# TP_IHM_BUZZER.net
KiCad netlist of a schematic drawn in Altium Designer
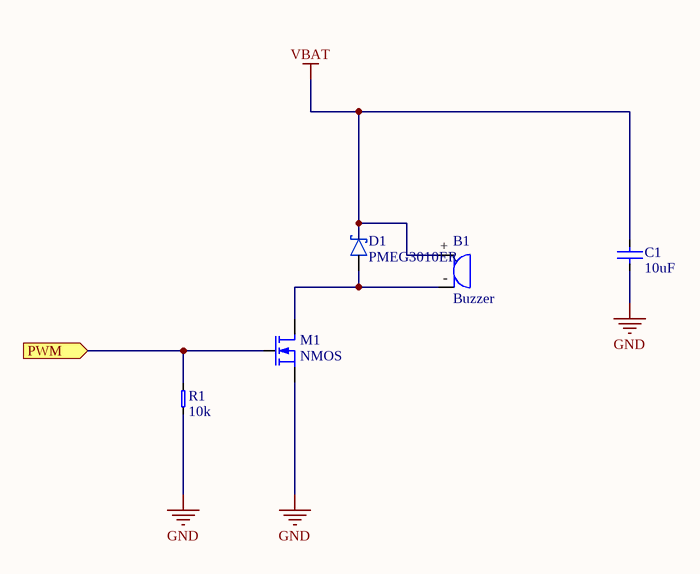
[diagram p0: TP_IHM_BUZZER.SchDoc]

(export (version "E")
  (design (tool "Eeschema 10.0.6"))
  (components
    (comp (ref "B1")
      (value "Buzzer")
      (footprint "SD160709")
      (description "TDK SD160709 Buzzer")
      (libsource (lib "TpGiven") (part "SD160709"))
    )
    (comp (ref "C1")
      (value "10uF")
      (footprint "0603_CAP_LD")
      (description "Ceramic Capacitor")
      (fields (field (name "Comment") "CerCap"))
      (libsource (lib "TpGiven") (part "CerCap"))
    )
    (comp (ref "D1")
      (value "PMEG3010ER")
      (footprint "SOD123W")
      (description "Nexperia 1A low Vf Mega Schottky barrier rectifier")
      (libsource (lib "TpGivenLib") (part "Schottky_PMEG3010ER"))
    )
    (comp (ref "M1")
      (value "NMOS")
      (footprint "MOSFET-SOT23")
      (description "N MOSFET")
      (libsource (lib "TpGiven") (part "N-MOSFET"))
    )
    (comp (ref "R1")
      (value "10k")
      (footprint "0603_RES_LD")
      (description "Resistor")
      (libsource (lib "TpGiven") (part "Resistor"))
    )
  )
  (nets
    (net (code "1") (name "/PWM") (class "Default")
      (node (ref "M1") (pin "G") (pinfunction "G_G") (pintype "passive"))
      (node (ref "R1") (pin "2") (pinfunction "2_2") (pintype "passive"))
    )
    (net (code "2") (name "GND") (class "Default")
      (node (ref "C1") (pin "1") (pinfunction "1_1") (pintype "passive"))
      (node (ref "M1") (pin "S") (pinfunction "S_S") (pintype "passive"))
      (node (ref "R1") (pin "1") (pinfunction "1_1") (pintype "passive"))
    )
    (net (code "3") (name "Net-(D1-1)") (class "Default")
      (node (ref "B1") (pin "-") (pinfunction "-_-") (pintype "passive"))
      (node (ref "D1") (pin "A") (pinfunction "1_A") (pintype "passive"))
      (node (ref "M1") (pin "D") (pinfunction "D_D") (pintype "passive"))
    )
    (net (code "4") (name "VBAT") (class "Default")
      (node (ref "B1") (pin "+") (pinfunction "+_+") (pintype "passive"))
      (node (ref "C1") (pin "2") (pinfunction "2_2") (pintype "passive"))
      (node (ref "D1") (pin "K") (pinfunction "2_K") (pintype "passive"))
    )
  )
)
